# ethernet.net
KiCad netlist of a schematic drawn in Altium Designer
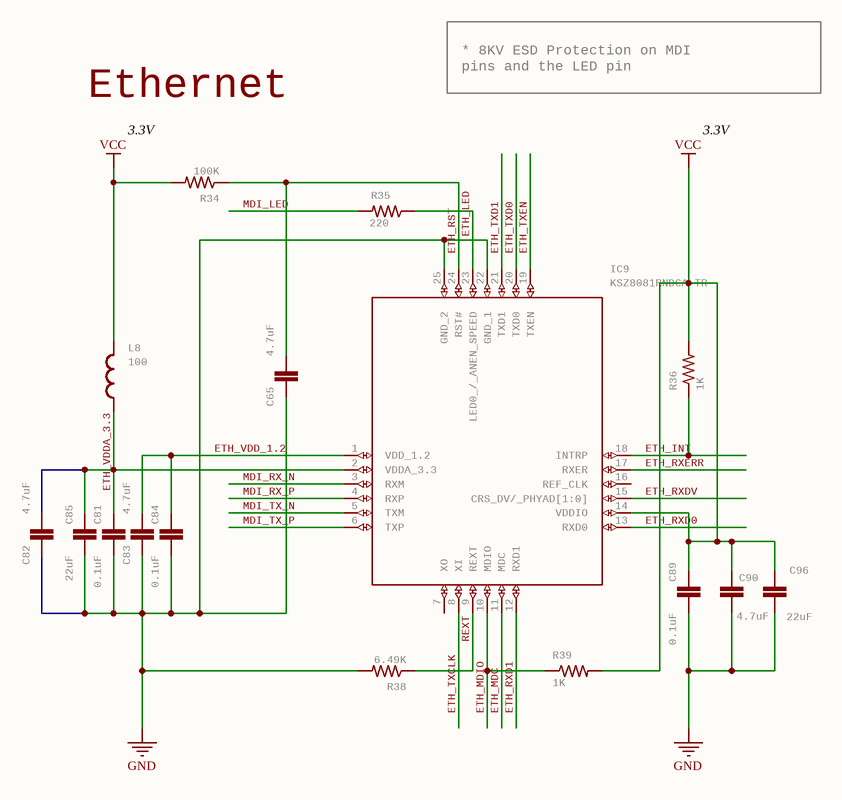
[diagram p0: ethernet.SchDoc]

(export (version "E")
  (design (tool "Eeschema 10.0.6"))
  (components
    (comp (ref "C65")
      (value "4.7uF")
      (footprint "0402-CAP")
      (description "CapacitorStandard 0603 ceramic capacitor, and 0.1\" leaded capacitor.")
      (fields (field (name "MPN") "JMK105BBJ475MV-F"))
      (libsource (lib "rt10") (part "CAP0402-CAP"))
    )
    (comp (ref "C81")
      (value "0.1uF")
      (footprint "0402-CAP")
      (description "CAPACITOR, European symbol")
      (fields (field (name "MPN") "C0402C104Z4VAC"))
      (libsource (lib "rt10") (part "C-EUC0201"))
    )
    (comp (ref "C82")
      (value "4.7uF")
      (footprint "0402-CAP")
      (description "CapacitorStandard 0603 ceramic capacitor, and 0.1\" leaded capacitor.")
      (fields (field (name "MPN") "JMK105BBJ475MV-F"))
      (libsource (lib "rt10") (part "CAP0402-CAP"))
    )
    (comp (ref "C83")
      (value "4.7uF")
      (footprint "0402-CAP")
      (description "CapacitorStandard 0603 ceramic capacitor, and 0.1\" leaded capacitor.")
      (fields (field (name "MPN") "JMK105BBJ475MV-F"))
      (libsource (lib "rt10") (part "CAP0402-CAP"))
    )
    (comp (ref "C84")
      (value "0.1uF")
      (footprint "0402-CAP")
      (description "CAPACITOR, European symbol")
      (fields (field (name "MPN") "C0402C104Z4VAC"))
      (libsource (lib "rt10") (part "C-EUC0201"))
    )
    (comp (ref "C85")
      (value "22uF")
      (footprint "0805")
      (fields (field (name "MPN") "CL21A226MQQNNNE"))
      (libsource (lib "rt10") (part "22UF-0805-6.3V-20%"))
    )
    (comp (ref "C89")
      (value "0.1uF")
      (footprint "0402-CAP")
      (description "CAPACITOR, European symbol")
      (fields (field (name "MPN") "C0402C104Z4VAC"))
      (libsource (lib "rt10") (part "C-EUC0201"))
    )
    (comp (ref "C90")
      (value "4.7uF")
      (footprint "0402-CAP")
      (description "CapacitorStandard 0603 ceramic capacitor, and 0.1\" leaded capacitor.")
      (fields (field (name "MPN") "JMK105BBJ475MV-F"))
      (libsource (lib "rt10") (part "CAP0402-CAP"))
    )
    (comp (ref "C96")
      (value "22uF")
      (footprint "0805")
      (fields (field (name "MPN") "CL21A226MQQNNNE"))
      (libsource (lib "rt10") (part "22UF-0805-6.3V-20%"))
    )
    (comp (ref "IC9")
      (value "KSZ8081RNDCA-TR")
      (footprint "QFN50P400X400X90-25N")
      (description "Ethernet ICs 10/100 BASE-TX Physical Layer Transceiver   Source:  Datasheet")
      (fields (field (name "MOUSER_PART_NUMBER") "998-KSZ8081RNDCATR"))
      (libsource (lib "rt10") (part "KSZ8081RNDCA-TR"))
    )
    (comp (ref "L8")
      (value "100")
      (footprint "C0402")
      (fields (field (name "MPN") "MFBM1V1005-101-R"))
      (libsource (lib "rt10") (part "INDUCTOR0402"))
    )
    (comp (ref "R34")
      (value "100K")
      (footprint "0402-RES")
      (description "ResistorBasic schematic elements and footprints for 0603, 1206, and PTH resistors.")
      (fields (field (name "MPN") "AC0402FR-07100KL"))
      (libsource (lib "rt10") (part "RESISTOR0402-RES"))
    )
    (comp (ref "R35")
      (value "220")
      (footprint "0402-RES")
      (description "ResistorBasic schematic elements and footprints for 0603, 1206, and PTH resistors.")
      (fields (field (name "MPN") "CRGCQ0402F220R"))
      (libsource (lib "rt10") (part "RESISTOR0402-RES"))
    )
    (comp (ref "R36")
      (value "1K")
      (footprint "0402-RES")
      (description "ResistorBasic schematic elements and footprints for 0603, 1206, and PTH resistors.")
      (fields (field (name "MPN") "CRCW04021K00FKEDC"))
      (libsource (lib "rt10") (part "RESISTOR0402-RES"))
    )
    (comp (ref "R38")
      (value "6.49K")
      (footprint "0402-RES")
      (description "ResistorBasic schematic elements and footprints for 0603, 1206, and PTH resistors.")
      (fields (field (name "MPN") "CR0402-FX-6491GLF"))
      (libsource (lib "rt10") (part "RESISTOR0402-RES"))
    )
    (comp (ref "R39")
      (value "1K")
      (footprint "0402-RES")
      (description "ResistorBasic schematic elements and footprints for 0603, 1206, and PTH resistors.")
      (fields (field (name "MPN") "CRCW04021K00FKEDC"))
      (libsource (lib "rt10") (part "RESISTOR0402-RES"))
    )
  )
  (nets
    (net (code "1") (name "/ETH_INT") (class "Default")
      (node (ref "IC9") (pin "18") (pinfunction "INTRP_18") (pintype "bidirectional"))
      (node (ref "R36") (pin "1") (pinfunction "1_1") (pintype "passive"))
    )
    (net (code "2") (name "/ETH_LED") (class "Default")
      (node (ref "IC9") (pin "23") (pinfunction "LED0_/_ANEN_SPEED_23") (pintype "bidirectional"))
      (node (ref "R35") (pin "1") (pinfunction "1_1") (pintype "passive"))
    )
    (net (code "3") (name "/ETH_MDC") (class "Default")
      (node (ref "IC9") (pin "11") (pinfunction "MDC_11") (pintype "bidirectional"))
    )
    (net (code "4") (name "/ETH_MDIO") (class "Default")
      (node (ref "IC9") (pin "10") (pinfunction "MDIO_10") (pintype "bidirectional"))
      (node (ref "R39") (pin "1") (pinfunction "1_1") (pintype "passive"))
    )
    (net (code "5") (name "/ETH_RST") (class "Default")
      (node (ref "C65") (pin "2") (pinfunction "2_2") (pintype "passive"))
      (node (ref "IC9") (pin "24") (pinfunction "RST#_24") (pintype "bidirectional"))
      (node (ref "R34") (pin "1") (pinfunction "1_1") (pintype "passive"))
    )
    (net (code "6") (name "/ETH_RXD0") (class "Default")
      (node (ref "IC9") (pin "13") (pinfunction "RXD0_13") (pintype "bidirectional"))
    )
    (net (code "7") (name "/ETH_RXD1") (class "Default")
      (node (ref "IC9") (pin "12") (pinfunction "RXD1_12") (pintype "bidirectional"))
    )
    (net (code "8") (name "/ETH_RXDV") (class "Default")
      (node (ref "IC9") (pin "15") (pinfunction "CRS_DV/_PHYAD[1:0]_15") (pintype "bidirectional"))
    )
    (net (code "9") (name "/ETH_RXERR") (class "Default")
      (node (ref "IC9") (pin "17") (pinfunction "RXER_17") (pintype "bidirectional"))
    )
    (net (code "10") (name "/ETH_TXCLK") (class "Default")
      (node (ref "IC9") (pin "8") (pinfunction "XI_8") (pintype "bidirectional"))
    )
    (net (code "11") (name "/ETH_TXD0") (class "Default")
      (node (ref "IC9") (pin "20") (pinfunction "TXD0_20") (pintype "bidirectional"))
    )
    (net (code "12") (name "/ETH_TXD1") (class "Default")
      (node (ref "IC9") (pin "21") (pinfunction "TXD1_21") (pintype "bidirectional"))
    )
    (net (code "13") (name "/ETH_TXEN") (class "Default")
      (node (ref "IC9") (pin "19") (pinfunction "TXEN_19") (pintype "bidirectional"))
    )
    (net (code "14") (name "/ETH_VDDA_3.3") (class "Default")
      (node (ref "C81") (pin "1") (pinfunction "1_1") (pintype "passive"))
      (node (ref "C82") (pin "2") (pinfunction "2_2") (pintype "passive"))
      (node (ref "C85") (pin "1") (pinfunction "1_1") (pintype "passive"))
      (node (ref "IC9") (pin "2") (pinfunction "VDDA_3.3_2") (pintype "bidirectional"))
      (node (ref "L8") (pin "1") (pinfunction "1_1") (pintype "passive"))
    )
    (net (code "15") (name "/ETH_VDD_1.2") (class "Default")
      (node (ref "C83") (pin "2") (pinfunction "2_2") (pintype "passive"))
      (node (ref "C84") (pin "1") (pinfunction "1_1") (pintype "passive"))
      (node (ref "IC9") (pin "1") (pinfunction "VDD_1.2_1") (pintype "bidirectional"))
    )
    (net (code "16") (name "/MDI_LED") (class "Default")
      (node (ref "R35") (pin "2") (pinfunction "2_2") (pintype "passive"))
    )
    (net (code "17") (name "/MDI_RX_N") (class "Default")
      (node (ref "IC9") (pin "3") (pinfunction "RXM_3") (pintype "bidirectional"))
    )
    (net (code "18") (name "/MDI_RX_P") (class "Default")
      (node (ref "IC9") (pin "4") (pinfunction "RXP_4") (pintype "bidirectional"))
    )
    (net (code "19") (name "/MDI_TX_N") (class "Default")
      (node (ref "IC9") (pin "5") (pinfunction "TXM_5") (pintype "bidirectional"))
    )
    (net (code "20") (name "/MDI_TX_P") (class "Default")
      (node (ref "IC9") (pin "6") (pinfunction "TXP_6") (pintype "bidirectional"))
    )
    (net (code "21") (name "/REXT") (class "Default")
      (node (ref "IC9") (pin "9") (pinfunction "REXT_9") (pintype "bidirectional"))
      (node (ref "R38") (pin "1") (pinfunction "1_1") (pintype "passive"))
    )
    (net (code "22") (name "GND") (class "Default")
      (node (ref "C65") (pin "1") (pinfunction "1_1") (pintype "passive"))
      (node (ref "C81") (pin "2") (pinfunction "2_2") (pintype "passive"))
      (node (ref "C82") (pin "1") (pinfunction "1_1") (pintype "passive"))
      (node (ref "C83") (pin "1") (pinfunction "1_1") (pintype "passive"))
      (node (ref "C84") (pin "2") (pinfunction "2_2") (pintype "passive"))
      (node (ref "C85") (pin "2") (pinfunction "2_2") (pintype "passive"))
      (node (ref "C89") (pin "2") (pinfunction "2_2") (pintype "passive"))
      (node (ref "C90") (pin "1") (pinfunction "1_1") (pintype "passive"))
      (node (ref "C96") (pin "2") (pinfunction "2_2") (pintype "passive"))
      (node (ref "IC9") (pin "22") (pinfunction "GND_1_22") (pintype "bidirectional"))
      (node (ref "IC9") (pin "25") (pinfunction "GND_2_25") (pintype "bidirectional"))
      (node (ref "R38") (pin "2") (pinfunction "2_2") (pintype "passive"))
    )
    (net (code "23") (name "VCC") (class "Default")
      (node (ref "C89") (pin "1") (pinfunction "1_1") (pintype "passive"))
      (node (ref "C90") (pin "2") (pinfunction "2_2") (pintype "passive"))
      (node (ref "C96") (pin "1") (pinfunction "1_1") (pintype "passive"))
      (node (ref "IC9") (pin "14") (pinfunction "VDDIO_14") (pintype "bidirectional"))
      (node (ref "L8") (pin "2") (pinfunction "2_2") (pintype "passive"))
      (node (ref "R34") (pin "2") (pinfunction "2_2") (pintype "passive"))
      (node (ref "R36") (pin "2") (pinfunction "2_2") (pintype "passive"))
      (node (ref "R39") (pin "2") (pinfunction "2_2") (pintype "passive"))
    )
    (net (code "24") (name "unconnected-(IC9-REF_CLK-Pad16)") (class "Default")
      (node (ref "IC9") (pin "16") (pinfunction "REF_CLK_16") (pintype "bidirectional"))
    )
    (net (code "25") (name "unconnected-(IC9-XO-Pad7)") (class "Default")
      (node (ref "IC9") (pin "7") (pinfunction "XO_7") (pintype "bidirectional"))
    )
  )
)
